# Control.net
KiCad netlist of a schematic drawn in EAGLE
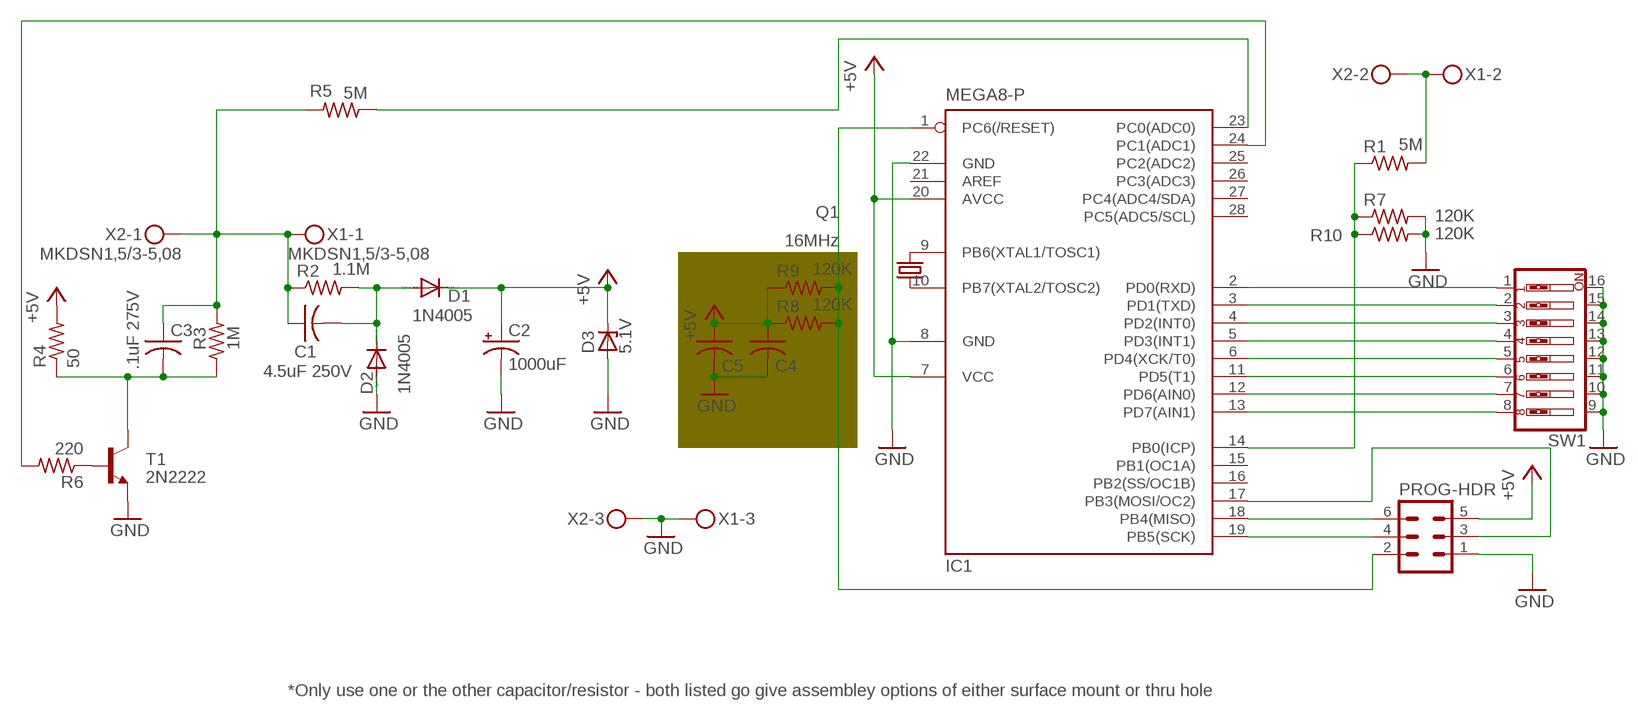
[diagram p0: schematic, sheet 1]

(export (version "E")
  (design (tool "Eeschema 10.0.6"))
  (components
    (comp (ref "C1")
      (value "4.5uF 250V")
      (footprint "eagle-import:C275-205X316")
      (libsource (lib "eagle-import") (part "C-US275-205X316"))
    )
    (comp (ref "C2")
      (value "1000uF")
      (footprint "eagle-import:E5-13")
      (libsource (lib "eagle-import") (part "CPOL-USE5-13"))
    )
    (comp (ref "C3")
      (value ".1uF 275V")
      (footprint "eagle-import:C150-091X182")
      (libsource (lib "eagle-import") (part "C-US150-091X182"))
    )
    (comp (ref "C4")
      (value "C-US025-024X044")
      (footprint "eagle-import:C025-024X044")
      (libsource (lib "eagle-import") (part "C-US025-024X044"))
    )
    (comp (ref "C5")
      (value "C-USC0402K")
      (footprint "eagle-import:C0402K")
      (libsource (lib "eagle-import") (part "C-USC0402K"))
    )
    (comp (ref "D1")
      (value "1N4005")
      (footprint "eagle-import:DO41-10")
      (libsource (lib "eagle-import") (part "1N4004"))
    )
    (comp (ref "D2")
      (value "1N4005")
      (footprint "eagle-import:DO41-10")
      (libsource (lib "eagle-import") (part "1N4004"))
    )
    (comp (ref "D3")
      (value "5.1V")
      (footprint "eagle-import:DO34Z7")
      (libsource (lib "eagle-import") (part "ZENER-DIODEDO34-7"))
    )
    (comp (ref "IC1")
      (value "MEGA8-P")
      (footprint "eagle-import:DIL28-3")
      (libsource (lib "eagle-import") (part "MEGA8-P"))
    )
    (comp (ref "PROG-HDR")
      (value "MA03-2")
      (footprint "eagle-import:MA03-2")
      (libsource (lib "eagle-import") (part "MA03-2"))
    )
    (comp (ref "Q1")
      (value "16MHz")
      (footprint "eagle-import:TC38H")
      (libsource (lib "eagle-import") (part "CRYSTALTC38H"))
    )
    (comp (ref "R1")
      (value "5M")
      (footprint "eagle-import:0414_15")
      (libsource (lib "eagle-import") (part "R-US_0414/15"))
    )
    (comp (ref "R2")
      (value "1.1M")
      (footprint "eagle-import:0414_15")
      (libsource (lib "eagle-import") (part "R-US_0414/15"))
    )
    (comp (ref "R3")
      (value "1M")
      (footprint "eagle-import:0411_12")
      (libsource (lib "eagle-import") (part "R-US_0411/12"))
    )
    (comp (ref "R4")
      (value "50")
      (footprint "eagle-import:0309_12")
      (libsource (lib "eagle-import") (part "R-US_0309/12"))
    )
    (comp (ref "R5")
      (value "5M")
      (footprint "eagle-import:0411_12")
      (libsource (lib "eagle-import") (part "R-US_0411/12"))
    )
    (comp (ref "R6")
      (value "220")
      (footprint "eagle-import:0411_12")
      (libsource (lib "eagle-import") (part "R-US_0411/12"))
    )
    (comp (ref "R7")
      (value "120K")
      (footprint "eagle-import:0207_7")
      (libsource (lib "eagle-import") (part "R-US_0207/7"))
    )
    (comp (ref "R8")
      (value "120K")
      (footprint "eagle-import:0207_7")
      (libsource (lib "eagle-import") (part "R-US_0207/7"))
    )
    (comp (ref "R9")
      (value "120K")
      (footprint "eagle-import:M0805")
      (libsource (lib "eagle-import") (part "R-US_M0805"))
    )
    (comp (ref "R10")
      (value "120K")
      (footprint "eagle-import:M0805")
      (libsource (lib "eagle-import") (part "R-US_M0805"))
    )
    (comp (ref "SW1")
      (value "SW_DIP-8")
      (footprint "eagle-import:EDG-08")
      (libsource (lib "eagle-import") (part "SW_DIP-8"))
    )
    (comp (ref "T1")
      (value "2N2222")
      (footprint "eagle-import:TO92")
      (libsource (lib "eagle-import") (part "-NPN-TO92"))
    )
    (comp (ref "X1")
      (value "MKDSN1,5/3-5,08")
      (footprint "eagle-import:MKDSN1,5_3-5,08")
      (libsource (lib "eagle-import") (part "MKDSN1,5/3-5,08"))
    )
    (comp (ref "X2")
      (value "MKDSN1,5/3-5,08")
      (footprint "eagle-import:MKDSN1,5_3-5,08")
      (libsource (lib "eagle-import") (part "MKDSN1,5/3-5,08"))
    )
  )
  (nets
    (net (code "1") (name "+5V") (class "Default")
      (node (ref "C2") (pin "+") (pinfunction "+_+") (pintype "passive"))
      (node (ref "C4") (pin "1") (pinfunction "1_1") (pintype "passive"))
      (node (ref "C5") (pin "1") (pinfunction "1_1") (pintype "passive"))
      (node (ref "D1") (pin "C") (pinfunction "C_C") (pintype "passive"))
      (node (ref "D3") (pin "C") (pinfunction "C_C") (pintype "passive"))
      (node (ref "IC1") (pin "20") (pinfunction "AVCC_20") (pintype "power_in"))
      (node (ref "IC1") (pin "7") (pinfunction "VCC_7") (pintype "power_in"))
      (node (ref "PROG-HDR") (pin "5") (pinfunction "5_5") (pintype "passive"))
      (node (ref "R4") (pin "2") (pinfunction "2_2") (pintype "passive"))
      (node (ref "R8") (pin "1") (pinfunction "1_1") (pintype "passive"))
      (node (ref "R9") (pin "1") (pinfunction "1_1") (pintype "passive"))
    )
    (net (code "2") (name "GND") (class "Default")
      (node (ref "C2") (pin "-") (pinfunction "-_-") (pintype "passive"))
      (node (ref "C4") (pin "2") (pinfunction "2_2") (pintype "passive"))
      (node (ref "C5") (pin "2") (pinfunction "2_2") (pintype "passive"))
      (node (ref "D2") (pin "A") (pinfunction "A_A") (pintype "passive"))
      (node (ref "D3") (pin "A") (pinfunction "A_A") (pintype "passive"))
      (node (ref "IC1") (pin "22") (pinfunction "GND_22") (pintype "power_in"))
      (node (ref "IC1") (pin "8") (pinfunction "GND_8") (pintype "power_in"))
      (node (ref "PROG-HDR") (pin "1") (pinfunction "1_1") (pintype "passive"))
      (node (ref "R10") (pin "2") (pinfunction "2_2") (pintype "passive"))
      (node (ref "R7") (pin "2") (pinfunction "2_2") (pintype "passive"))
      (node (ref "SW1") (pin "10") (pinfunction "10_10") (pintype "passive"))
      (node (ref "SW1") (pin "11") (pinfunction "11_11") (pintype "passive"))
      (node (ref "SW1") (pin "12") (pinfunction "12_12") (pintype "passive"))
      (node (ref "SW1") (pin "13") (pinfunction "13_13") (pintype "passive"))
      (node (ref "SW1") (pin "14") (pinfunction "14_14") (pintype "passive"))
      (node (ref "SW1") (pin "15") (pinfunction "15_15") (pintype "passive"))
      (node (ref "SW1") (pin "16") (pinfunction "16_16") (pintype "passive"))
      (node (ref "SW1") (pin "9") (pinfunction "9_9") (pintype "passive"))
      (node (ref "T1") (pin "1") (pinfunction "E_1") (pintype "passive"))
      (node (ref "X1") (pin "3") (pinfunction "KL_3") (pintype "passive"))
      (node (ref "X2") (pin "3") (pinfunction "KL_3") (pintype "passive"))
    )
    (net (code "3") (name "Net-(C1-Pad2)") (class "Default")
      (node (ref "C1") (pin "2") (pinfunction "2_2") (pintype "passive"))
      (node (ref "D1") (pin "A") (pinfunction "A_A") (pintype "passive"))
      (node (ref "D2") (pin "C") (pinfunction "C_C") (pintype "passive"))
      (node (ref "R2") (pin "2") (pinfunction "2_2") (pintype "passive"))
    )
    (net (code "4") (name "Net-(IC1-PB0(ICP))") (class "Default")
      (node (ref "IC1") (pin "14") (pinfunction "PB0(ICP)_14") (pintype "bidirectional"))
      (node (ref "R1") (pin "1") (pinfunction "1_1") (pintype "passive"))
      (node (ref "R10") (pin "1") (pinfunction "1_1") (pintype "passive"))
      (node (ref "R7") (pin "1") (pinfunction "1_1") (pintype "passive"))
    )
    (net (code "5") (name "Net-(IC1-PB3(MOSI{slash}OC2))") (class "Default")
      (node (ref "IC1") (pin "17") (pinfunction "PB3(MOSI/OC2)_17") (pintype "bidirectional"))
      (node (ref "PROG-HDR") (pin "3") (pinfunction "3_3") (pintype "passive"))
    )
    (net (code "6") (name "Net-(IC1-PB4(MISO))") (class "Default")
      (node (ref "IC1") (pin "18") (pinfunction "PB4(MISO)_18") (pintype "bidirectional"))
      (node (ref "PROG-HDR") (pin "6") (pinfunction "6_6") (pintype "passive"))
    )
    (net (code "7") (name "Net-(IC1-PB5(SCK))") (class "Default")
      (node (ref "IC1") (pin "19") (pinfunction "PB5(SCK)_19") (pintype "bidirectional"))
      (node (ref "PROG-HDR") (pin "4") (pinfunction "4_4") (pintype "passive"))
    )
    (net (code "8") (name "Net-(IC1-PB6(XTAL1{slash}TOSC1))") (class "Default")
      (node (ref "IC1") (pin "9") (pinfunction "PB6(XTAL1/TOSC1)_9") (pintype "bidirectional"))
      (node (ref "Q1") (pin "2") (pinfunction "2_2") (pintype "passive"))
    )
    (net (code "9") (name "Net-(IC1-PB7(XTAL2{slash}TOSC2))") (class "Default")
      (node (ref "IC1") (pin "10") (pinfunction "PB7(XTAL2/TOSC2)_10") (pintype "bidirectional"))
      (node (ref "Q1") (pin "1") (pinfunction "1_1") (pintype "passive"))
    )
    (net (code "10") (name "Net-(IC1-PC0(ADC0))") (class "Default")
      (node (ref "IC1") (pin "23") (pinfunction "PC0(ADC0)_23") (pintype "bidirectional"))
      (node (ref "R5") (pin "1") (pinfunction "1_1") (pintype "passive"))
    )
    (net (code "11") (name "Net-(IC1-PC1(ADC1))") (class "Default")
      (node (ref "IC1") (pin "24") (pinfunction "PC1(ADC1)_24") (pintype "bidirectional"))
      (node (ref "R6") (pin "2") (pinfunction "2_2") (pintype "passive"))
    )
    (net (code "12") (name "Net-(IC1-PC6({slash}RESET))") (class "Default")
      (node (ref "IC1") (pin "1") (pinfunction "PC6(/RESET)_1") (pintype "bidirectional"))
      (node (ref "PROG-HDR") (pin "2") (pinfunction "2_2") (pintype "passive"))
      (node (ref "R8") (pin "2") (pinfunction "2_2") (pintype "passive"))
      (node (ref "R9") (pin "2") (pinfunction "2_2") (pintype "passive"))
    )
    (net (code "13") (name "Net-(IC1-PD0(RXD))") (class "Default")
      (node (ref "IC1") (pin "2") (pinfunction "PD0(RXD)_2") (pintype "bidirectional"))
      (node (ref "SW1") (pin "1") (pinfunction "1_1") (pintype "passive"))
    )
    (net (code "14") (name "Net-(IC1-PD1(TXD))") (class "Default")
      (node (ref "IC1") (pin "3") (pinfunction "PD1(TXD)_3") (pintype "bidirectional"))
      (node (ref "SW1") (pin "2") (pinfunction "2_2") (pintype "passive"))
    )
    (net (code "15") (name "Net-(IC1-PD2(INT0))") (class "Default")
      (node (ref "IC1") (pin "4") (pinfunction "PD2(INT0)_4") (pintype "bidirectional"))
      (node (ref "SW1") (pin "3") (pinfunction "3_3") (pintype "passive"))
    )
    (net (code "16") (name "Net-(IC1-PD3(INT1))") (class "Default")
      (node (ref "IC1") (pin "5") (pinfunction "PD3(INT1)_5") (pintype "bidirectional"))
      (node (ref "SW1") (pin "4") (pinfunction "4_4") (pintype "passive"))
    )
    (net (code "17") (name "Net-(IC1-PD4(XCK{slash}T0))") (class "Default")
      (node (ref "IC1") (pin "6") (pinfunction "PD4(XCK/T0)_6") (pintype "bidirectional"))
      (node (ref "SW1") (pin "5") (pinfunction "5_5") (pintype "passive"))
    )
    (net (code "18") (name "Net-(IC1-PD5(T1))") (class "Default")
      (node (ref "IC1") (pin "11") (pinfunction "PD5(T1)_11") (pintype "bidirectional"))
      (node (ref "SW1") (pin "6") (pinfunction "6_6") (pintype "passive"))
    )
    (net (code "19") (name "Net-(IC1-PD6(AIN0))") (class "Default")
      (node (ref "IC1") (pin "12") (pinfunction "PD6(AIN0)_12") (pintype "bidirectional"))
      (node (ref "SW1") (pin "7") (pinfunction "7_7") (pintype "passive"))
    )
    (net (code "20") (name "Net-(IC1-PD7(AIN1))") (class "Default")
      (node (ref "IC1") (pin "13") (pinfunction "PD7(AIN1)_13") (pintype "bidirectional"))
      (node (ref "SW1") (pin "8") (pinfunction "8_8") (pintype "passive"))
    )
    (net (code "21") (name "Net-(T1-B)") (class "Default")
      (node (ref "R6") (pin "1") (pinfunction "1_1") (pintype "passive"))
      (node (ref "T1") (pin "2") (pinfunction "B_2") (pintype "passive"))
    )
    (net (code "22") (name "Net-(T1-C)") (class "Default")
      (node (ref "C3") (pin "2") (pinfunction "2_2") (pintype "passive"))
      (node (ref "R3") (pin "1") (pinfunction "1_1") (pintype "passive"))
      (node (ref "R4") (pin "1") (pinfunction "1_1") (pintype "passive"))
      (node (ref "T1") (pin "3") (pinfunction "C_3") (pintype "passive"))
    )
    (net (code "23") (name "Net-(X1A-KL)") (class "Default")
      (node (ref "C1") (pin "1") (pinfunction "1_1") (pintype "passive"))
      (node (ref "C3") (pin "1") (pinfunction "1_1") (pintype "passive"))
      (node (ref "R2") (pin "1") (pinfunction "1_1") (pintype "passive"))
      (node (ref "R3") (pin "2") (pinfunction "2_2") (pintype "passive"))
      (node (ref "R5") (pin "2") (pinfunction "2_2") (pintype "passive"))
      (node (ref "X1") (pin "1") (pinfunction "KL_1") (pintype "passive"))
      (node (ref "X2") (pin "1") (pinfunction "KL_1") (pintype "passive"))
    )
    (net (code "24") (name "Net-(X1B-KL)") (class "Default")
      (node (ref "R1") (pin "2") (pinfunction "2_2") (pintype "passive"))
      (node (ref "X1") (pin "2") (pinfunction "KL_2") (pintype "passive"))
      (node (ref "X2") (pin "2") (pinfunction "KL_2") (pintype "passive"))
    )
    (net (code "25") (name "unconnected-(IC1-AREF-Pad21)") (class "Default")
      (node (ref "IC1") (pin "21") (pinfunction "AREF_21") (pintype "passive"))
    )
    (net (code "26") (name "unconnected-(IC1-PB1(OC1A)-Pad15)") (class "Default")
      (node (ref "IC1") (pin "15") (pinfunction "PB1(OC1A)_15") (pintype "bidirectional"))
    )
    (net (code "27") (name "unconnected-(IC1-PB2(SS{slash}OC1B)-Pad16)") (class "Default")
      (node (ref "IC1") (pin "16") (pinfunction "PB2(SS/OC1B)_16") (pintype "bidirectional"))
    )
    (net (code "28") (name "unconnected-(IC1-PC2(ADC2)-Pad25)") (class "Default")
      (node (ref "IC1") (pin "25") (pinfunction "PC2(ADC2)_25") (pintype "bidirectional"))
    )
    (net (code "29") (name "unconnected-(IC1-PC3(ADC3)-Pad26)") (class "Default")
      (node (ref "IC1") (pin "26") (pinfunction "PC3(ADC3)_26") (pintype "bidirectional"))
    )
    (net (code "30") (name "unconnected-(IC1-PC4(ADC4{slash}SDA)-Pad27)") (class "Default")
      (node (ref "IC1") (pin "27") (pinfunction "PC4(ADC4/SDA)_27") (pintype "bidirectional"))
    )
    (net (code "31") (name "unconnected-(IC1-PC5(ADC5{slash}SCL)-Pad28)") (class "Default")
      (node (ref "IC1") (pin "28") (pinfunction "PC5(ADC5/SCL)_28") (pintype "bidirectional"))
    )
  )
)
